# design.net
KiCad netlist of a schematic drawn in Altium Designer
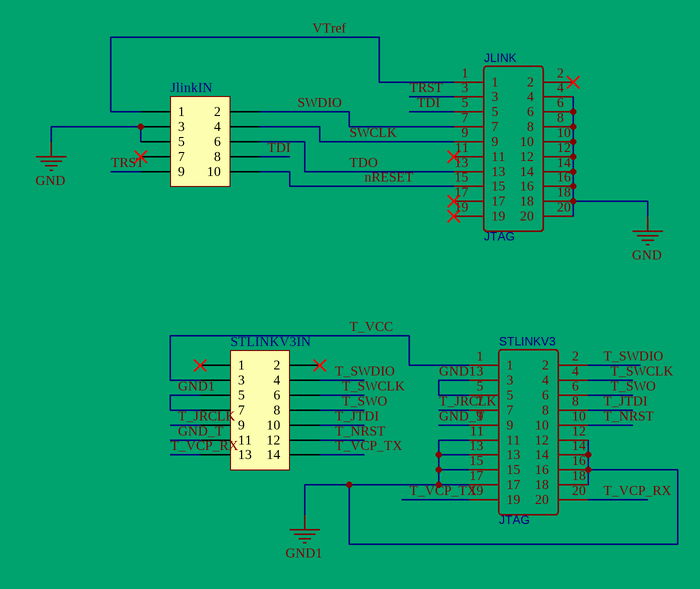
[diagram p0: 转接板.SchDoc]

(export (version "E")
  (design (tool "Eeschema 10.0.6"))
  (components
    (comp (ref "JLINK")
      (value "JTAG")
      (footprint "IDC-TH_20P-P2.54-V-R2-C10-S2.54")
      (fields
        (field (name "BOM_SUPPLIER PART") "C221051")
        (field (name "BOM_MANUFACTURER PART") "Z-231011020106")
        (field (name "CONTRIBUTOR") "LCSC")
      )
      (libsource (lib "Miscellaneous Devices LC") (part "JTAG"))
    )
    (comp (ref "JlinkIN")
      (value "Header 5X2")
      (footprint "HDR-SMD_10P-P1.27-V-R2-C5-S5.00")
      (description "Header, 5-Pin, Dual row")
      (fields (field (name "PUBLISHER") "Altium Limited"))
      (libsource (lib "Miscellaneous Connectors") (part "Header 5X2"))
    )
    (comp (ref "STLINKV3")
      (value "JTAG")
      (footprint "IDC-TH_20P-P2.54-V-R2-C10-S2.54")
      (fields
        (field (name "BOM_SUPPLIER PART") "C221051")
        (field (name "BOM_MANUFACTURER PART") "Z-231011020106")
        (field (name "CONTRIBUTOR") "LCSC")
      )
      (libsource (lib "Miscellaneous Devices LC") (part "JTAG"))
    )
    (comp (ref "STLINKV3IN")
      (value "Header 7X2")
      (footprint "STDC14(SOIC)")
      (description "Header, 7-Pin, Dual row")
      (fields (field (name "PUBLISHER") "Altium Limited"))
      (libsource (lib "Miscellaneous Connectors") (part "Header 7X2"))
    )
  )
  (nets
    (net (code "2") (name "/GND_T") (class "Default")
      (node (ref "STLINKV3") (pin "9") (pinfunction "9_9") (pintype "passive"))
      (node (ref "STLINKV3IN") (pin "11") (pinfunction "11_11") (pintype "passive"))
    )
    (net (code "3") (name "/SWCLK") (class "Default")
      (node (ref "JLINK") (pin "9") (pinfunction "9_9") (pintype "passive"))
      (node (ref "JlinkIN") (pin "4") (pinfunction "4_4") (pintype "passive"))
    )
    (net (code "4") (name "/SWDIO") (class "Default")
      (node (ref "JLINK") (pin "7") (pinfunction "7_7") (pintype "passive"))
      (node (ref "JlinkIN") (pin "2") (pinfunction "2_2") (pintype "passive"))
    )
    (net (code "5") (name "/TDI") (class "Default")
      (node (ref "JLINK") (pin "5") (pinfunction "5_5") (pintype "passive"))
      (node (ref "JlinkIN") (pin "8") (pinfunction "8_8") (pintype "passive"))
    )
    (net (code "6") (name "/TDO") (class "Default")
      (node (ref "JLINK") (pin "13") (pinfunction "13_13") (pintype "passive"))
      (node (ref "JlinkIN") (pin "6") (pinfunction "6_6") (pintype "passive"))
    )
    (net (code "7") (name "/TRST") (class "Default")
      (node (ref "JLINK") (pin "3") (pinfunction "3_3") (pintype "passive"))
      (node (ref "JlinkIN") (pin "9") (pinfunction "9_9") (pintype "passive"))
    )
    (net (code "8") (name "/T_JRCLK") (class "Default")
      (node (ref "STLINKV3") (pin "7") (pinfunction "7_7") (pintype "passive"))
      (node (ref "STLINKV3IN") (pin "9") (pinfunction "9_9") (pintype "passive"))
    )
    (net (code "9") (name "/T_JTDI") (class "Default")
      (node (ref "STLINKV3") (pin "8") (pinfunction "8_8") (pintype "passive"))
      (node (ref "STLINKV3IN") (pin "10") (pinfunction "10_10") (pintype "passive"))
    )
    (net (code "10") (name "/T_NRST") (class "Default")
      (node (ref "STLINKV3") (pin "10") (pinfunction "10_10") (pintype "passive"))
      (node (ref "STLINKV3IN") (pin "12") (pinfunction "12_12") (pintype "passive"))
    )
    (net (code "11") (name "/T_SWCLK") (class "Default")
      (node (ref "STLINKV3") (pin "4") (pinfunction "4_4") (pintype "passive"))
      (node (ref "STLINKV3IN") (pin "6") (pinfunction "6_6") (pintype "passive"))
    )
    (net (code "12") (name "/T_SWDIO") (class "Default")
      (node (ref "STLINKV3") (pin "2") (pinfunction "2_2") (pintype "passive"))
      (node (ref "STLINKV3IN") (pin "4") (pinfunction "4_4") (pintype "passive"))
    )
    (net (code "13") (name "/T_SWO") (class "Default")
      (node (ref "STLINKV3") (pin "6") (pinfunction "6_6") (pintype "passive"))
      (node (ref "STLINKV3IN") (pin "8") (pinfunction "8_8") (pintype "passive"))
    )
    (net (code "14") (name "/T_VCC") (class "Default")
      (node (ref "STLINKV3") (pin "1") (pinfunction "1_1") (pintype "passive"))
      (node (ref "STLINKV3IN") (pin "3") (pinfunction "3_3") (pintype "passive"))
    )
    (net (code "15") (name "/T_VCP_RX") (class "Default")
      (node (ref "STLINKV3") (pin "20") (pinfunction "20_20") (pintype "passive"))
      (node (ref "STLINKV3IN") (pin "13") (pinfunction "13_13") (pintype "passive"))
    )
    (net (code "16") (name "/T_VCP_TX") (class "Default")
      (node (ref "STLINKV3") (pin "19") (pinfunction "19_19") (pintype "passive"))
      (node (ref "STLINKV3IN") (pin "14") (pinfunction "14_14") (pintype "passive"))
    )
    (net (code "17") (name "/VTref") (class "Default")
      (node (ref "JLINK") (pin "1") (pinfunction "1_1") (pintype "passive"))
      (node (ref "JlinkIN") (pin "1") (pinfunction "1_1") (pintype "passive"))
    )
    (net (code "18") (name "/nRESET") (class "Default")
      (node (ref "JLINK") (pin "15") (pinfunction "15_15") (pintype "passive"))
      (node (ref "JlinkIN") (pin "10") (pinfunction "10_10") (pintype "passive"))
    )
    (net (code "19") (name "GND") (class "Default")
      (node (ref "JLINK") (pin "10") (pinfunction "10_10") (pintype "passive"))
      (node (ref "JLINK") (pin "12") (pinfunction "12_12") (pintype "passive"))
      (node (ref "JLINK") (pin "14") (pinfunction "14_14") (pintype "passive"))
      (node (ref "JLINK") (pin "16") (pinfunction "16_16") (pintype "passive"))
      (node (ref "JLINK") (pin "18") (pinfunction "18_18") (pintype "passive"))
      (node (ref "JLINK") (pin "20") (pinfunction "20_20") (pintype "passive"))
      (node (ref "JLINK") (pin "4") (pinfunction "4_4") (pintype "passive"))
      (node (ref "JLINK") (pin "6") (pinfunction "6_6") (pintype "passive"))
      (node (ref "JLINK") (pin "8") (pinfunction "8_8") (pintype "passive"))
      (node (ref "JlinkIN") (pin "3") (pinfunction "3_3") (pintype "passive"))
      (node (ref "JlinkIN") (pin "5") (pinfunction "5_5") (pintype "passive"))
    )
    (net (code "20") (name "GND1") (class "Default")
      (node (ref "STLINKV3") (pin "11") (pinfunction "11_11") (pintype "passive"))
      (node (ref "STLINKV3") (pin "12") (pinfunction "12_12") (pintype "passive"))
      (node (ref "STLINKV3") (pin "13") (pinfunction "13_13") (pintype "passive"))
      (node (ref "STLINKV3") (pin "14") (pinfunction "14_14") (pintype "passive"))
      (node (ref "STLINKV3") (pin "15") (pinfunction "15_15") (pintype "passive"))
      (node (ref "STLINKV3") (pin "16") (pinfunction "16_16") (pintype "passive"))
      (node (ref "STLINKV3") (pin "17") (pinfunction "17_17") (pintype "passive"))
      (node (ref "STLINKV3") (pin "18") (pinfunction "18_18") (pintype "passive"))
      (node (ref "STLINKV3") (pin "3") (pinfunction "3_3") (pintype "passive"))
      (node (ref "STLINKV3") (pin "5") (pinfunction "5_5") (pintype "passive"))
      (node (ref "STLINKV3IN") (pin "5") (pinfunction "5_5") (pintype "passive"))
      (node (ref "STLINKV3IN") (pin "7") (pinfunction "7_7") (pintype "passive"))
    )
    (net (code "21") (name "unconnected-(JLINK-Pad2)") (class "Default")
      (node (ref "JLINK") (pin "2") (pinfunction "2_2") (pintype "passive+no_connect"))
    )
    (net (code "22") (name "unconnected-(JLINK-Pad11)") (class "Default")
      (node (ref "JLINK") (pin "11") (pinfunction "11_11") (pintype "passive+no_connect"))
    )
    (net (code "23") (name "unconnected-(JLINK-Pad17)") (class "Default")
      (node (ref "JLINK") (pin "17") (pinfunction "17_17") (pintype "passive+no_connect"))
    )
    (net (code "24") (name "unconnected-(JLINK-Pad19)") (class "Default")
      (node (ref "JLINK") (pin "19") (pinfunction "19_19") (pintype "passive+no_connect"))
    )
    (net (code "25") (name "unconnected-(JlinkIN-Pad7)") (class "Default")
      (node (ref "JlinkIN") (pin "7") (pinfunction "7_7") (pintype "passive+no_connect"))
    )
    (net (code "26") (name "unconnected-(STLINKV3IN-Pad1)") (class "Default")
      (node (ref "STLINKV3IN") (pin "1") (pinfunction "1_1") (pintype "passive+no_connect"))
    )
    (net (code "27") (name "unconnected-(STLINKV3IN-Pad2)") (class "Default")
      (node (ref "STLINKV3IN") (pin "2") (pinfunction "2_2") (pintype "passive+no_connect"))
    )
  )
)
